# PTW_Mosfet.net
KiCad netlist of a schematic drawn in Altium Designer
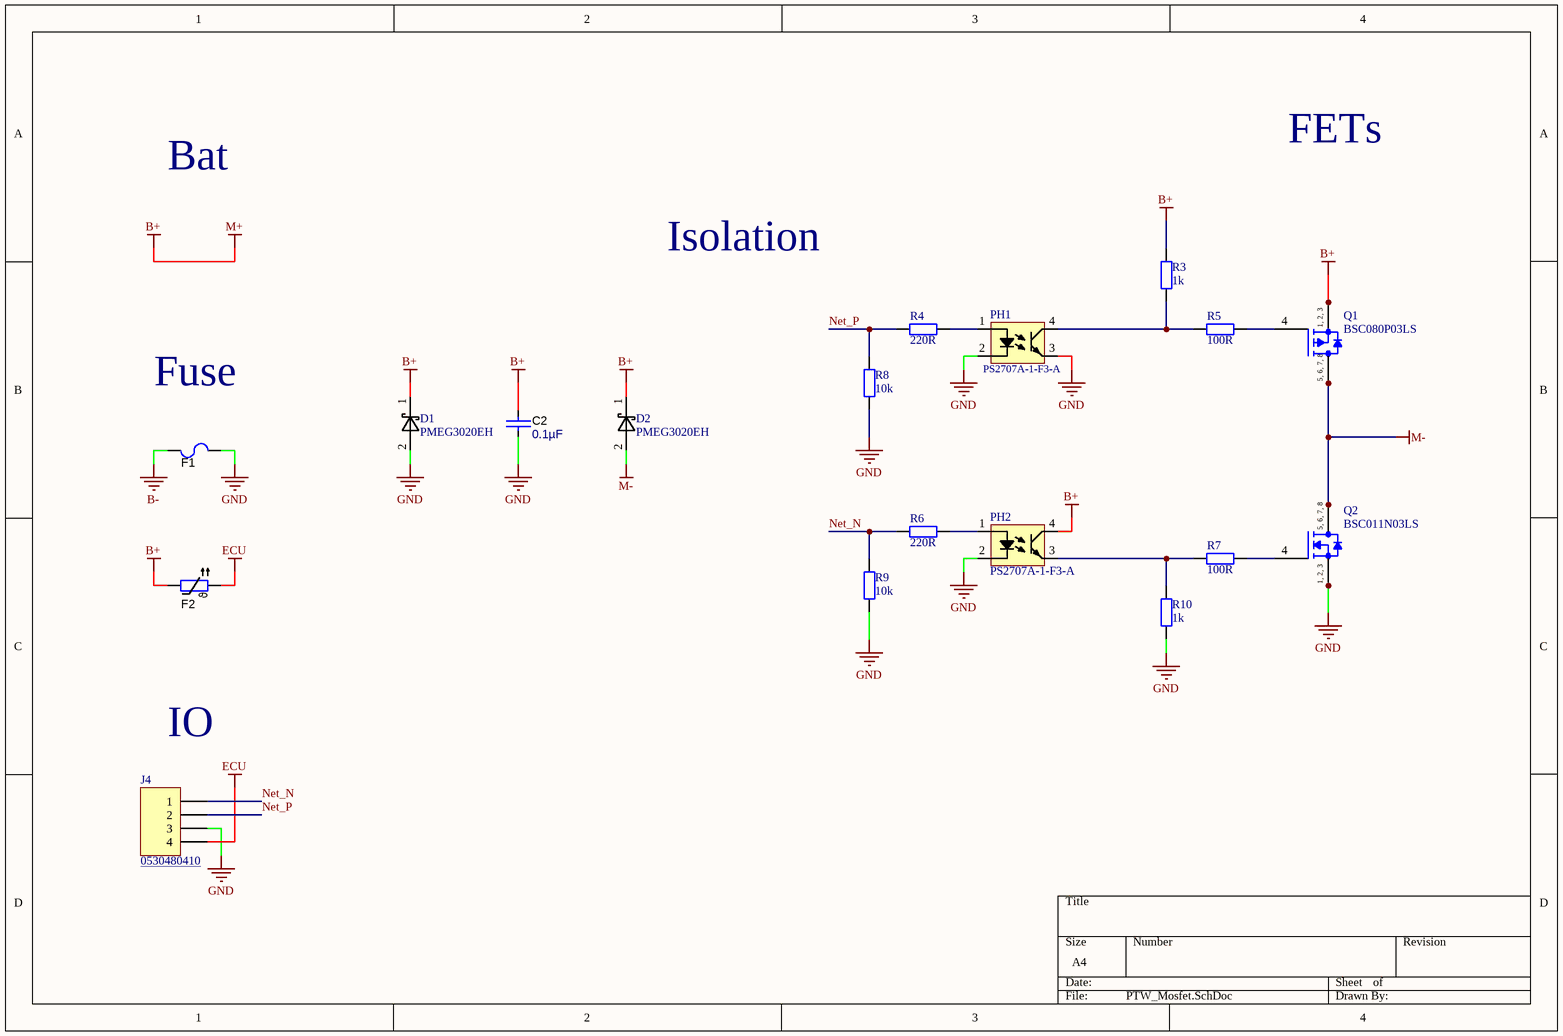
[diagram p0: PTW_Mosfet.SchDoc]

(export (version "E")
  (design (tool "Eeschema 10.0.6"))
  (components
    (comp (ref "C2")
      (value "0.1µF")
      (footprint "CAPC0402(1005)60_N")
      (description "Capacitor SMD Cer 0.1µF 10% 25V X5R 0402")
      (fields (field (name "TOLERANCE") "10%") (field (name "MANUFACTURER") "TDK"))
      (libsource (lib "CAPs") (part "CAPC_25V_X5R_0.47µF_0402"))
    )
    (comp (ref "D1")
      (value "PMEG3020EH")
      (footprint "SOD123F")
      (description "Diode Shottky 30V, 2A")
      (fields (field (name "MANUFACTURER") "ON Semiconductor"))
      (libsource (lib "Diode") (part "PMEG3020EH"))
    )
    (comp (ref "D2")
      (value "PMEG3020EH")
      (footprint "SOD123F")
      (description "Diode Shottky 30V, 2A")
      (fields (field (name "MANUFACTURER") "ON Semiconductor"))
      (libsource (lib "Diode") (part "PMEG3020EH"))
    )
    (comp (ref "F1")
      (value "Keystone3569")
      (footprint "Keystone3569")
      (description "Keystone Blade Fuse SMD")
      (libsource (lib "PTC") (part "Keystone3569"))
    )
    (comp (ref "F2")
      (value "MF-FSMF050X-2")
      (footprint "0603 _N")
      (description "PTC 6V 0.5A (h), 1s (t) @ 1A")
      (libsource (lib "PTC") (part "MF-FSMF050X-2"))
    )
    (comp (ref "J4")
      (value "0530480410")
      (footprint "0530480410")
      (description "Molex Picoblade, 3Pin THT Straight")
      (libsource (lib "Connector") (part "0530480410"))
    )
    (comp (ref "PH1")
      (value "PS2707A-1-F3-A")
      (footprint "SOP-4")
      (description "1-ch optocoupler 3.75kV")
      (fields (field (name "MANUFACTURER") "NEC"))
      (libsource (lib "OPTO") (part "PS2707A-1-F3-A"))
    )
    (comp (ref "PH2")
      (value "PS2707A-1-F3-A")
      (footprint "SOP-4")
      (description "1-ch optocoupler 3.75kV")
      (fields (field (name "MANUFACTURER") "NEC"))
      (libsource (lib "OPTO") (part "PS2707A-1-F3-A"))
    )
    (comp (ref "Q1")
      (value "BSC080P03LS")
      (footprint "TDSON-8-1-Infineon")
      (description "30V P-Channel OptiMOSPower-MOSFET")
      (libsource (lib "FETs") (part "BSC080P03LS"))
    )
    (comp (ref "Q2")
      (value "BSC011N03LS")
      (footprint "TDSON-8-1-Infineon")
      (description "30V N-Channel OptiMOSPower-MOSFET")
      (libsource (lib "FETs") (part "BSC011N03LS"))
    )
    (comp (ref "R3")
      (value "1k")
      (footprint "RESC0402(1005)_N")
      (description "R_0402")
      (fields (field (name "TOLERANCE") "±?%") (field (name "MANUFACTURER") "?"))
      (libsource (lib "") (part "RES_0402_1"))
    )
    (comp (ref "R4")
      (value "220R")
      (footprint "RESC0402(1005)_N")
      (description "R_0402")
      (fields (field (name "TOLERANCE") "±?%") (field (name "MANUFACTURER") "?"))
      (libsource (lib "RES") (part "RES_0402"))
    )
    (comp (ref "R5")
      (value "100R")
      (footprint "RESC0402(1005)_N")
      (description "R_0402")
      (fields (field (name "TOLERANCE") "±?%") (field (name "MANUFACTURER") "?"))
      (libsource (lib "RES") (part "RES_0402"))
    )
    (comp (ref "R6")
      (value "220R")
      (footprint "RESC0402(1005)_N")
      (description "R_0402")
      (fields (field (name "TOLERANCE") "±?%") (field (name "MANUFACTURER") "?"))
      (libsource (lib "RES") (part "RES_0402"))
    )
    (comp (ref "R7")
      (value "100R")
      (footprint "RESC0402(1005)_N")
      (description "R_0402")
      (fields (field (name "TOLERANCE") "±?%") (field (name "MANUFACTURER") "?"))
      (libsource (lib "RES") (part "RES_0402"))
    )
    (comp (ref "R8")
      (value "10k")
      (footprint "RESC0402(1005)_N")
      (description "R_0402")
      (fields (field (name "TOLERANCE") "±?%") (field (name "MANUFACTURER") "?"))
      (libsource (lib "") (part "RES_0402_1"))
    )
    (comp (ref "R9")
      (value "10k")
      (footprint "RESC0402(1005)_N")
      (description "R_0402")
      (fields (field (name "TOLERANCE") "±?%") (field (name "MANUFACTURER") "?"))
      (libsource (lib "") (part "RES_0402_1"))
    )
    (comp (ref "R10")
      (value "1k")
      (footprint "RESC0402(1005)_N")
      (description "R_0402")
      (fields (field (name "TOLERANCE") "±?%") (field (name "MANUFACTURER") "?"))
      (libsource (lib "") (part "RES_0402_1"))
    )
  )
  (nets
    (net (code "1") (name "/Net_N") (class "Default")
      (node (ref "J4") (pin "1") (pinfunction "1_1") (pintype "passive"))
      (node (ref "R6") (pin "1") (pinfunction "1_1") (pintype "passive"))
      (node (ref "R9") (pin "1") (pinfunction "1_1") (pintype "passive"))
    )
    (net (code "2") (name "/Net_P") (class "Default")
      (node (ref "J4") (pin "2") (pinfunction "2_2") (pintype "passive"))
      (node (ref "R4") (pin "1") (pinfunction "1_1") (pintype "passive"))
      (node (ref "R8") (pin "1") (pinfunction "1_1") (pintype "passive"))
    )
    (net (code "3") (name "B+") (class "Default")
      (node (ref "C2") (pin "1") (pintype "passive"))
      (node (ref "D1") (pin "1") (pinfunction "1_1") (pintype "passive"))
      (node (ref "D2") (pin "1") (pinfunction "1_1") (pintype "passive"))
      (node (ref "F2") (pin "1") (pinfunction "1_1") (pintype "passive"))
      (node (ref "PH2") (pin "4") (pinfunction "4_4") (pintype "passive"))
      (node (ref "Q1") (pin "1") (pinfunction "S_1") (pintype "passive"))
      (node (ref "Q1") (pin "2") (pinfunction "S_2") (pintype "passive"))
      (node (ref "Q1") (pin "3") (pinfunction "S_3") (pintype "passive"))
      (node (ref "R3") (pin "1") (pinfunction "1_1") (pintype "passive"))
    )
    (net (code "4") (name "B-") (class "Default")
      (node (ref "F1") (pin "1") (pinfunction "1_1") (pintype "passive"))
    )
    (net (code "5") (name "ECU") (class "Default")
      (node (ref "F2") (pin "2") (pinfunction "2_2") (pintype "passive"))
      (node (ref "J4") (pin "4") (pinfunction "4_4") (pintype "passive"))
    )
    (net (code "6") (name "GND") (class "Default")
      (node (ref "C2") (pin "2") (pintype "passive"))
      (node (ref "D1") (pin "2") (pinfunction "2_2") (pintype "passive"))
      (node (ref "F1") (pin "2") (pinfunction "2_2") (pintype "passive"))
      (node (ref "J4") (pin "3") (pinfunction "3_3") (pintype "passive"))
      (node (ref "PH1") (pin "2") (pinfunction "2_2") (pintype "passive"))
      (node (ref "PH1") (pin "3") (pinfunction "3_3") (pintype "passive"))
      (node (ref "PH2") (pin "2") (pinfunction "2_2") (pintype "passive"))
      (node (ref "Q2") (pin "1") (pinfunction "S_1") (pintype "passive"))
      (node (ref "Q2") (pin "2") (pinfunction "S_2") (pintype "passive"))
      (node (ref "Q2") (pin "3") (pinfunction "S_3") (pintype "passive"))
      (node (ref "R10") (pin "2") (pinfunction "2_2") (pintype "passive"))
      (node (ref "R8") (pin "2") (pinfunction "2_2") (pintype "passive"))
      (node (ref "R9") (pin "2") (pinfunction "2_2") (pintype "passive"))
    )
    (net (code "7") (name "M-") (class "Default")
      (node (ref "D2") (pin "2") (pinfunction "2_2") (pintype "passive"))
      (node (ref "Q1") (pin "5") (pinfunction "D_5") (pintype "passive"))
      (node (ref "Q1") (pin "6") (pinfunction "D_6") (pintype "passive"))
      (node (ref "Q1") (pin "7") (pinfunction "D_7") (pintype "passive"))
      (node (ref "Q1") (pin "8") (pinfunction "D_8") (pintype "passive"))
      (node (ref "Q1") (pin "9") (pinfunction "D_9") (pintype "passive"))
      (node (ref "Q2") (pin "5") (pinfunction "D_5") (pintype "passive"))
      (node (ref "Q2") (pin "6") (pinfunction "D_6") (pintype "passive"))
      (node (ref "Q2") (pin "7") (pinfunction "D_7") (pintype "passive"))
      (node (ref "Q2") (pin "8") (pinfunction "D_8") (pintype "passive"))
      (node (ref "Q2") (pin "9") (pinfunction "D_9") (pintype "passive"))
    )
    (net (code "8") (name "Net-(PH1-Pad1)") (class "Default")
      (node (ref "PH1") (pin "1") (pinfunction "1_1") (pintype "passive"))
      (node (ref "R4") (pin "2") (pinfunction "2_2") (pintype "passive"))
    )
    (net (code "9") (name "Net-(PH1-Pad4)") (class "Default")
      (node (ref "PH1") (pin "4") (pinfunction "4_4") (pintype "passive"))
      (node (ref "R3") (pin "2") (pinfunction "2_2") (pintype "passive"))
      (node (ref "R5") (pin "1") (pinfunction "1_1") (pintype "passive"))
    )
    (net (code "10") (name "Net-(PH2-Pad1)") (class "Default")
      (node (ref "PH2") (pin "1") (pinfunction "1_1") (pintype "passive"))
      (node (ref "R6") (pin "2") (pinfunction "2_2") (pintype "passive"))
    )
    (net (code "11") (name "Net-(PH2-Pad3)") (class "Default")
      (node (ref "PH2") (pin "3") (pinfunction "3_3") (pintype "passive"))
      (node (ref "R10") (pin "1") (pinfunction "1_1") (pintype "passive"))
      (node (ref "R7") (pin "1") (pinfunction "1_1") (pintype "passive"))
    )
    (net (code "12") (name "Net-(Q1-G)") (class "Default")
      (node (ref "Q1") (pin "4") (pinfunction "G_4") (pintype "passive"))
      (node (ref "R5") (pin "2") (pinfunction "2_2") (pintype "passive"))
    )
    (net (code "13") (name "Net-(Q2-G)") (class "Default")
      (node (ref "Q2") (pin "4") (pinfunction "G_4") (pintype "passive"))
      (node (ref "R7") (pin "2") (pinfunction "2_2") (pintype "passive"))
    )
  )
)
